# TMP37_0402.net
KiCad netlist of a schematic drawn in EAGLE
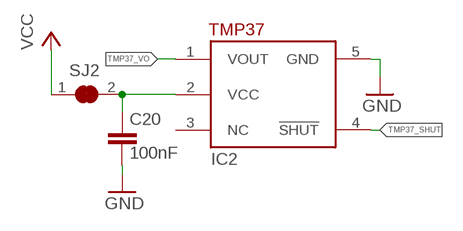
[diagram p0: schematic, sheet 1]

(export (version "E")
  (design (tool "Eeschema 10.0.6"))
  (components
    (comp (ref "C20")
      (value "100nF")
      (footprint "eagle-import:C0402")
      (libsource (lib "eagle-import") (part "C-EUC0402"))
    )
    (comp (ref "IC2")
      (value "TMP37GRTZ-REEL7")
      (footprint "eagle-import:SOT-23-5")
      (libsource (lib "eagle-import") (part "TMP37"))
    )
    (comp (ref "SJ2")
      (value "SOLDERJUMPER_CLOSED")
      (footprint "eagle-import:SOLDERJUMPER_CLOSEDWIRE")
      (libsource (lib "eagle-import") (part "SOLDERJUMPER_CLOSED"))
    )
  )
  (nets
    (net (code "1") (name "GND") (class "Default")
      (node (ref "C20") (pin "2") (pinfunction "2_2") (pintype "passive"))
      (node (ref "IC2") (pin "5") (pinfunction "GND_5") (pintype "input"))
    )
    (net (code "2") (name "Net-(IC2-VCC)") (class "Default")
      (node (ref "C20") (pin "1") (pinfunction "1_1") (pintype "passive"))
      (node (ref "IC2") (pin "2") (pinfunction "VCC_2") (pintype "power_in"))
      (node (ref "SJ2") (pin "2") (pinfunction "2_2") (pintype "passive"))
    )
    (net (code "3") (name "TMP37_SHUT") (class "Default")
      (node (ref "IC2") (pin "4") (pinfunction "~{SHUT}_4") (pintype "power_in"))
    )
    (net (code "4") (name "TMP37_VO") (class "Default")
      (node (ref "IC2") (pin "1") (pinfunction "VOUT_1") (pintype "input"))
    )
    (net (code "5") (name "VCC") (class "Default")
      (node (ref "SJ2") (pin "1") (pinfunction "1_1") (pintype "passive"))
    )
    (net (code "6") (name "unconnected-(IC2-NC-Pad3)") (class "Default")
      (node (ref "IC2") (pin "3") (pinfunction "NC_3") (pintype "bidirectional"))
    )
  )
)
